# vco-8038.net
KiCad netlist of a schematic drawn in EAGLE
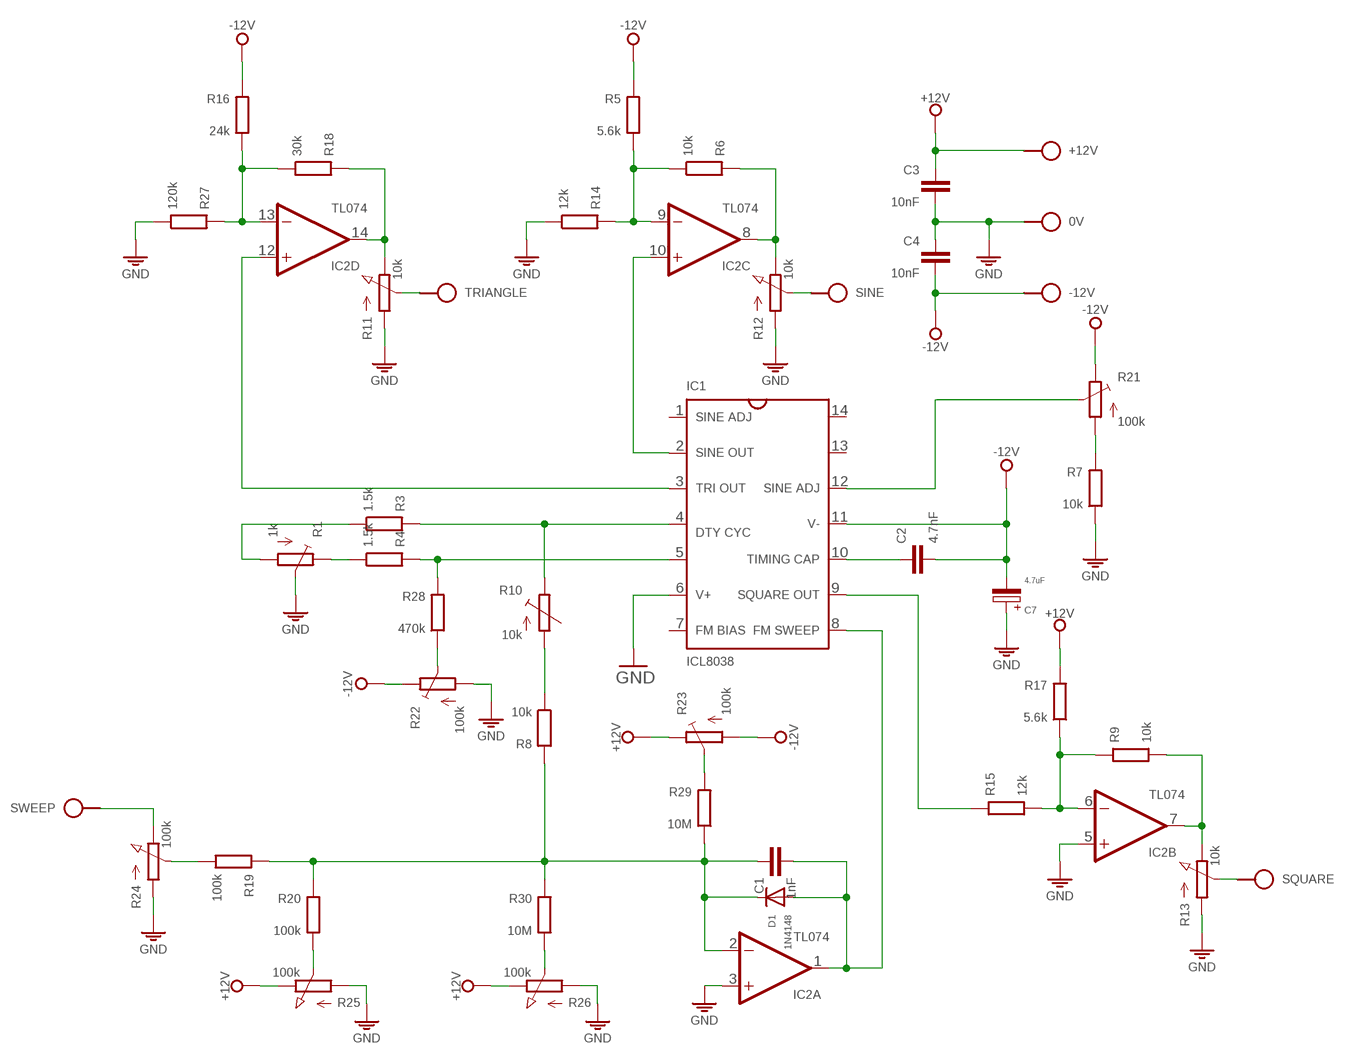
[diagram p0: schematic, sheet 1]

(export (version "E")
  (design (tool "Eeschema 10.0.6"))
  (components
    (comp (ref "+12V")
      (value "SPAD")
      (footprint "eagle-import:SPAD")
      (libsource (lib "eagle-import") (part "SPAD"))
    )
    (comp (ref "-12V")
      (value "SPAD")
      (footprint "eagle-import:SPAD")
      (libsource (lib "eagle-import") (part "SPAD"))
    )
    (comp (ref "0V")
      (value "SPAD")
      (footprint "eagle-import:SPAD")
      (libsource (lib "eagle-import") (part "SPAD"))
    )
    (comp (ref "C1")
      (value "1nF")
      (footprint "eagle-import:C050-020X036")
      (libsource (lib "eagle-import") (part "C050-020X036"))
    )
    (comp (ref "C2")
      (value "4.7nF")
      (footprint "eagle-import:C050-020X036")
      (libsource (lib "eagle-import") (part "C050-020X036"))
    )
    (comp (ref "C3")
      (value "10nF")
      (footprint "eagle-import:C050-020X036")
      (libsource (lib "eagle-import") (part "C050-020X036"))
    )
    (comp (ref "C4")
      (value "10nF")
      (footprint "eagle-import:C050-020X036")
      (libsource (lib "eagle-import") (part "C050-020X036"))
    )
    (comp (ref "C7")
      (value "4.7uF")
      (footprint "eagle-import:E5-5_V")
      (libsource (lib "eagle-import") (part "CPOLE5-5/V"))
    )
    (comp (ref "D1")
      (value "1N4148")
      (footprint "eagle-import:DO34-7")
      (libsource (lib "eagle-import") (part "1N414834-7"))
    )
    (comp (ref "IC1")
      (value "ICL8038")
      (footprint "eagle-import:DIL14")
      (libsource (lib "eagle-import") (part "ICL8038"))
    )
    (comp (ref "IC2")
      (value "TL074")
      (footprint "eagle-import:DIL14")
      (libsource (lib "eagle-import") (part "TL074P"))
    )
    (comp (ref "R1")
      (value "1k")
      (footprint "eagle-import:R-TRIM")
      (libsource (lib "eagle-import") (part "TRIMR-TRIM"))
    )
    (comp (ref "R3")
      (value "1.5k")
      (footprint "eagle-import:0204_7")
      (libsource (lib "eagle-import") (part "R0204/7"))
    )
    (comp (ref "R4")
      (value "1.5k")
      (footprint "eagle-import:0204_7")
      (libsource (lib "eagle-import") (part "R0204/7"))
    )
    (comp (ref "R5")
      (value "5.6k")
      (footprint "eagle-import:0204_7")
      (libsource (lib "eagle-import") (part "R0204/7"))
    )
    (comp (ref "R6")
      (value "10k")
      (footprint "eagle-import:0204_7")
      (libsource (lib "eagle-import") (part "R0204/7"))
    )
    (comp (ref "R7")
      (value "10k")
      (footprint "eagle-import:0204_7")
      (libsource (lib "eagle-import") (part "R0204/7"))
    )
    (comp (ref "R8")
      (value "10k")
      (footprint "eagle-import:0204_7")
      (libsource (lib "eagle-import") (part "R0204/7"))
    )
    (comp (ref "R9")
      (value "10k")
      (footprint "eagle-import:0204_7")
      (libsource (lib "eagle-import") (part "R0204/7"))
    )
    (comp (ref "R10")
      (value "10k")
      (footprint "eagle-import:R-TRIM")
      (libsource (lib "eagle-import") (part "TRIM-2R-TRIM-2"))
    )
    (comp (ref "R11")
      (value "10k")
      (footprint "eagle-import:POT")
      (libsource (lib "eagle-import") (part "POT"))
    )
    (comp (ref "R12")
      (value "10k")
      (footprint "eagle-import:POT")
      (libsource (lib "eagle-import") (part "POT"))
    )
    (comp (ref "R13")
      (value "10k")
      (footprint "eagle-import:POT")
      (libsource (lib "eagle-import") (part "POT"))
    )
    (comp (ref "R14")
      (value "12k")
      (footprint "eagle-import:0204_7")
      (libsource (lib "eagle-import") (part "R0204/7"))
    )
    (comp (ref "R15")
      (value "12k")
      (footprint "eagle-import:0204_7")
      (libsource (lib "eagle-import") (part "R0204/7"))
    )
    (comp (ref "R16")
      (value "24k")
      (footprint "eagle-import:0204_7")
      (libsource (lib "eagle-import") (part "R0204/7"))
    )
    (comp (ref "R17")
      (value "5.6k")
      (footprint "eagle-import:0204_7")
      (libsource (lib "eagle-import") (part "R0204/7"))
    )
    (comp (ref "R18")
      (value "30k")
      (footprint "eagle-import:0204_7")
      (libsource (lib "eagle-import") (part "R0204/7"))
    )
    (comp (ref "R19")
      (value "100k")
      (footprint "eagle-import:0204_7")
      (libsource (lib "eagle-import") (part "R0204/7"))
    )
    (comp (ref "R20")
      (value "100k")
      (footprint "eagle-import:0204_7")
      (libsource (lib "eagle-import") (part "R0204/7"))
    )
    (comp (ref "R21")
      (value "100k")
      (footprint "eagle-import:R-TRIM")
      (libsource (lib "eagle-import") (part "TRIMR-TRIM"))
    )
    (comp (ref "R22")
      (value "100k")
      (footprint "eagle-import:R-TRIM")
      (libsource (lib "eagle-import") (part "TRIMR-TRIM"))
    )
    (comp (ref "R23")
      (value "100k")
      (footprint "eagle-import:R-TRIM")
      (libsource (lib "eagle-import") (part "TRIMR-TRIM"))
    )
    (comp (ref "R24")
      (value "100k")
      (footprint "eagle-import:POT")
      (libsource (lib "eagle-import") (part "POT"))
    )
    (comp (ref "R25")
      (value "100k")
      (footprint "eagle-import:POT")
      (libsource (lib "eagle-import") (part "POT"))
    )
    (comp (ref "R26")
      (value "100k")
      (footprint "eagle-import:POT")
      (libsource (lib "eagle-import") (part "POT"))
    )
    (comp (ref "R27")
      (value "120k")
      (footprint "eagle-import:0204_7")
      (libsource (lib "eagle-import") (part "R0204/7"))
    )
    (comp (ref "R28")
      (value "470k")
      (footprint "eagle-import:0204_7")
      (libsource (lib "eagle-import") (part "R0204/7"))
    )
    (comp (ref "R29")
      (value "10M")
      (footprint "eagle-import:0204_7")
      (libsource (lib "eagle-import") (part "R0204/7"))
    )
    (comp (ref "R30")
      (value "10M")
      (footprint "eagle-import:0204_7")
      (libsource (lib "eagle-import") (part "R0204/7"))
    )
    (comp (ref "SINE")
      (value "SPAD")
      (footprint "eagle-import:SPAD")
      (libsource (lib "eagle-import") (part "SPAD"))
    )
    (comp (ref "SQUARE")
      (value "SPAD")
      (footprint "eagle-import:SPAD")
      (libsource (lib "eagle-import") (part "SPAD"))
    )
    (comp (ref "SWEEP")
      (value "SPAD")
      (footprint "eagle-import:SPAD")
      (libsource (lib "eagle-import") (part "SPAD"))
    )
    (comp (ref "TRIANGLE")
      (value "SPAD")
      (footprint "eagle-import:SPAD")
      (libsource (lib "eagle-import") (part "SPAD"))
    )
  )
  (nets
    (net (code "1") (name "+12V") (class "Default")
      (node (ref "+12V") (pin "1") (pinfunction "P$1_1") (pintype "bidirectional"))
      (node (ref "C3") (pin "1") (pinfunction "1_1") (pintype "passive"))
      (node (ref "R17") (pin "2") (pinfunction "2_2") (pintype "passive"))
      (node (ref "R23") (pin "3") (pinfunction "E_3") (pintype "passive"))
      (node (ref "R25") (pin "3") (pinfunction "E_3") (pintype "passive"))
      (node (ref "R26") (pin "3") (pinfunction "E_3") (pintype "passive"))
    )
    (net (code "2") (name "-12V") (class "Default")
      (node (ref "-12V") (pin "1") (pinfunction "P$1_1") (pintype "bidirectional"))
      (node (ref "C2") (pin "2") (pinfunction "2_2") (pintype "passive"))
      (node (ref "C4") (pin "2") (pinfunction "2_2") (pintype "passive"))
      (node (ref "C7") (pin "-") (pinfunction "-_-") (pintype "passive"))
      (node (ref "IC1") (pin "11") (pinfunction "V-_11") (pintype "bidirectional"))
      (node (ref "R16") (pin "2") (pinfunction "2_2") (pintype "passive"))
      (node (ref "R21") (pin "3") (pinfunction "E_3") (pintype "passive"))
      (node (ref "R22") (pin "3") (pinfunction "E_3") (pintype "passive"))
      (node (ref "R23") (pin "1") (pinfunction "A_1") (pintype "passive"))
      (node (ref "R5") (pin "2") (pinfunction "2_2") (pintype "passive"))
    )
    (net (code "3") (name "GND") (class "Default")
      (node (ref "0V") (pin "1") (pinfunction "P$1_1") (pintype "bidirectional"))
      (node (ref "C3") (pin "2") (pinfunction "2_2") (pintype "passive"))
      (node (ref "C4") (pin "1") (pinfunction "1_1") (pintype "passive"))
      (node (ref "C7") (pin "+") (pinfunction "+_+") (pintype "passive"))
      (node (ref "IC1") (pin "6") (pinfunction "V+_6") (pintype "bidirectional"))
      (node (ref "IC2") (pin "3") (pinfunction "+IN_3") (pintype "input"))
      (node (ref "IC2") (pin "5") (pinfunction "+IN_5") (pintype "input"))
      (node (ref "R1") (pin "2") (pinfunction "S_2") (pintype "passive"))
      (node (ref "R11") (pin "1") (pinfunction "A_1") (pintype "passive"))
      (node (ref "R12") (pin "1") (pinfunction "A_1") (pintype "passive"))
      (node (ref "R13") (pin "1") (pinfunction "A_1") (pintype "passive"))
      (node (ref "R14") (pin "1") (pinfunction "1_1") (pintype "passive"))
      (node (ref "R22") (pin "1") (pinfunction "A_1") (pintype "passive"))
      (node (ref "R24") (pin "1") (pinfunction "A_1") (pintype "passive"))
      (node (ref "R25") (pin "1") (pinfunction "A_1") (pintype "passive"))
      (node (ref "R26") (pin "1") (pinfunction "A_1") (pintype "passive"))
      (node (ref "R27") (pin "1") (pinfunction "1_1") (pintype "passive"))
      (node (ref "R7") (pin "1") (pinfunction "1_1") (pintype "passive"))
    )
    (net (code "4") (name "Net-(IC1-DUTY_1)") (class "Default")
      (node (ref "IC1") (pin "4") (pinfunction "DUTY_1_4") (pintype "bidirectional"))
      (node (ref "R10") (pin "1") (pinfunction "1_1") (pintype "passive"))
      (node (ref "R10") (pin "2") (pinfunction "1_2") (pintype "passive"))
      (node (ref "R3") (pin "2") (pinfunction "2_2") (pintype "passive"))
    )
    (net (code "5") (name "Net-(IC1-DUTY_2)") (class "Default")
      (node (ref "IC1") (pin "5") (pinfunction "DUTY_2_5") (pintype "bidirectional"))
      (node (ref "R28") (pin "2") (pinfunction "2_2") (pintype "passive"))
      (node (ref "R4") (pin "2") (pinfunction "2_2") (pintype "passive"))
    )
    (net (code "6") (name "Net-(IC1-FM_SWEEP)") (class "Default")
      (node (ref "C1") (pin "2") (pinfunction "2_2") (pintype "passive"))
      (node (ref "D1") (pin "A") (pinfunction "A_A") (pintype "passive"))
      (node (ref "IC1") (pin "8") (pinfunction "FM_SWEEP_8") (pintype "bidirectional"))
      (node (ref "IC2") (pin "1") (pinfunction "OUT_1") (pintype "output"))
    )
    (net (code "7") (name "Net-(IC1-SINE_ADJ_2)") (class "Default")
      (node (ref "IC1") (pin "12") (pinfunction "SINE_ADJ_2_12") (pintype "bidirectional"))
      (node (ref "R21") (pin "2") (pinfunction "S_2") (pintype "passive"))
    )
    (net (code "8") (name "Net-(IC1-SINE_OUT)") (class "Default")
      (node (ref "IC1") (pin "2") (pinfunction "SINE_OUT_2") (pintype "bidirectional"))
      (node (ref "IC2") (pin "10") (pinfunction "+IN_10") (pintype "input"))
    )
    (net (code "9") (name "Net-(IC1-SQR_OUT)") (class "Default")
      (node (ref "IC1") (pin "9") (pinfunction "SQR_OUT_9") (pintype "bidirectional"))
      (node (ref "R15") (pin "2") (pinfunction "2_2") (pintype "passive"))
    )
    (net (code "10") (name "Net-(IC1-TIMING_CAP)") (class "Default")
      (node (ref "C2") (pin "1") (pinfunction "1_1") (pintype "passive"))
      (node (ref "IC1") (pin "10") (pinfunction "TIMING_CAP_10") (pintype "bidirectional"))
    )
    (net (code "11") (name "Net-(IC1-TRI_OUT)") (class "Default")
      (node (ref "IC1") (pin "3") (pinfunction "TRI_OUT_3") (pintype "bidirectional"))
      (node (ref "IC2") (pin "12") (pinfunction "+IN_12") (pintype "input"))
    )
    (net (code "12") (name "Net-(IC2A--IN)") (class "Default")
      (node (ref "C1") (pin "1") (pinfunction "1_1") (pintype "passive"))
      (node (ref "D1") (pin "C") (pinfunction "C_C") (pintype "passive"))
      (node (ref "IC2") (pin "2") (pinfunction "-IN_2") (pintype "input"))
      (node (ref "R19") (pin "2") (pinfunction "2_2") (pintype "passive"))
      (node (ref "R20") (pin "2") (pinfunction "2_2") (pintype "passive"))
      (node (ref "R29") (pin "1") (pinfunction "1_1") (pintype "passive"))
      (node (ref "R30") (pin "2") (pinfunction "2_2") (pintype "passive"))
      (node (ref "R8") (pin "2") (pinfunction "2_2") (pintype "passive"))
    )
    (net (code "13") (name "Net-(IC2B--IN)") (class "Default")
      (node (ref "IC2") (pin "6") (pinfunction "-IN_6") (pintype "input"))
      (node (ref "R15") (pin "1") (pinfunction "1_1") (pintype "passive"))
      (node (ref "R17") (pin "1") (pinfunction "1_1") (pintype "passive"))
      (node (ref "R9") (pin "2") (pinfunction "2_2") (pintype "passive"))
    )
    (net (code "14") (name "Net-(IC2B-OUT)") (class "Default")
      (node (ref "IC2") (pin "7") (pinfunction "OUT_7") (pintype "output"))
      (node (ref "R13") (pin "3") (pinfunction "E_3") (pintype "passive"))
      (node (ref "R9") (pin "1") (pinfunction "1_1") (pintype "passive"))
    )
    (net (code "15") (name "Net-(IC2C--IN)") (class "Default")
      (node (ref "IC2") (pin "9") (pinfunction "-IN_9") (pintype "input"))
      (node (ref "R14") (pin "2") (pinfunction "2_2") (pintype "passive"))
      (node (ref "R5") (pin "1") (pinfunction "1_1") (pintype "passive"))
      (node (ref "R6") (pin "1") (pinfunction "1_1") (pintype "passive"))
    )
    (net (code "16") (name "Net-(IC2C-OUT)") (class "Default")
      (node (ref "IC2") (pin "8") (pinfunction "OUT_8") (pintype "output"))
      (node (ref "R12") (pin "3") (pinfunction "E_3") (pintype "passive"))
      (node (ref "R6") (pin "2") (pinfunction "2_2") (pintype "passive"))
    )
    (net (code "17") (name "Net-(IC2D--IN)") (class "Default")
      (node (ref "IC2") (pin "13") (pinfunction "-IN_13") (pintype "input"))
      (node (ref "R16") (pin "1") (pinfunction "1_1") (pintype "passive"))
      (node (ref "R18") (pin "1") (pinfunction "1_1") (pintype "passive"))
      (node (ref "R27") (pin "2") (pinfunction "2_2") (pintype "passive"))
    )
    (net (code "18") (name "Net-(IC2D-OUT)") (class "Default")
      (node (ref "IC2") (pin "14") (pinfunction "OUT_14") (pintype "output"))
      (node (ref "R11") (pin "3") (pinfunction "E_3") (pintype "passive"))
      (node (ref "R18") (pin "2") (pinfunction "2_2") (pintype "passive"))
    )
    (net (code "19") (name "Net-(R1-A)") (class "Default")
      (node (ref "R1") (pin "1") (pinfunction "A_1") (pintype "passive"))
      (node (ref "R3") (pin "1") (pinfunction "1_1") (pintype "passive"))
    )
    (net (code "20") (name "Net-(R1-E)") (class "Default")
      (node (ref "R1") (pin "3") (pinfunction "E_3") (pintype "passive"))
      (node (ref "R4") (pin "1") (pinfunction "1_1") (pintype "passive"))
    )
    (net (code "21") (name "Net-(R10-2)") (class "Default")
      (node (ref "R10") (pin "3") (pinfunction "2_3") (pintype "passive"))
      (node (ref "R8") (pin "1") (pinfunction "1_1") (pintype "passive"))
    )
    (net (code "22") (name "Net-(R11-S)") (class "Default")
      (node (ref "R11") (pin "2") (pinfunction "S_2") (pintype "passive"))
      (node (ref "TRIANGLE") (pin "1") (pinfunction "P$1_1") (pintype "bidirectional"))
    )
    (net (code "23") (name "Net-(R12-S)") (class "Default")
      (node (ref "R12") (pin "2") (pinfunction "S_2") (pintype "passive"))
      (node (ref "SINE") (pin "1") (pinfunction "P$1_1") (pintype "bidirectional"))
    )
    (net (code "24") (name "Net-(R13-S)") (class "Default")
      (node (ref "R13") (pin "2") (pinfunction "S_2") (pintype "passive"))
      (node (ref "SQUARE") (pin "1") (pinfunction "P$1_1") (pintype "bidirectional"))
    )
    (net (code "25") (name "Net-(R21-A)") (class "Default")
      (node (ref "R21") (pin "1") (pinfunction "A_1") (pintype "passive"))
      (node (ref "R7") (pin "2") (pinfunction "2_2") (pintype "passive"))
    )
    (net (code "26") (name "Net-(R22-S)") (class "Default")
      (node (ref "R22") (pin "2") (pinfunction "S_2") (pintype "passive"))
      (node (ref "R28") (pin "1") (pinfunction "1_1") (pintype "passive"))
    )
    (net (code "27") (name "Net-(R23-S)") (class "Default")
      (node (ref "R23") (pin "2") (pinfunction "S_2") (pintype "passive"))
      (node (ref "R29") (pin "2") (pinfunction "2_2") (pintype "passive"))
    )
    (net (code "28") (name "Net-(R24-E)") (class "Default")
      (node (ref "R24") (pin "3") (pinfunction "E_3") (pintype "passive"))
      (node (ref "SWEEP") (pin "1") (pinfunction "P$1_1") (pintype "bidirectional"))
    )
    (net (code "29") (name "Net-(R24-S)") (class "Default")
      (node (ref "R19") (pin "1") (pinfunction "1_1") (pintype "passive"))
      (node (ref "R24") (pin "2") (pinfunction "S_2") (pintype "passive"))
    )
    (net (code "30") (name "Net-(R25-S)") (class "Default")
      (node (ref "R20") (pin "1") (pinfunction "1_1") (pintype "passive"))
      (node (ref "R25") (pin "2") (pinfunction "S_2") (pintype "passive"))
    )
    (net (code "31") (name "Net-(R26-S)") (class "Default")
      (node (ref "R26") (pin "2") (pinfunction "S_2") (pintype "passive"))
      (node (ref "R30") (pin "1") (pinfunction "1_1") (pintype "passive"))
    )
    (net (code "32") (name "unconnected-(IC1-FM_BIAS-Pad7)") (class "Default")
      (node (ref "IC1") (pin "7") (pinfunction "FM_BIAS_7") (pintype "bidirectional"))
    )
    (net (code "33") (name "unconnected-(IC1-NC_1-Pad13)") (class "Default")
      (node (ref "IC1") (pin "13") (pinfunction "NC_1_13") (pintype "bidirectional"))
    )
    (net (code "34") (name "unconnected-(IC1-NC_2-Pad14)") (class "Default")
      (node (ref "IC1") (pin "14") (pinfunction "NC_2_14") (pintype "bidirectional"))
    )
    (net (code "35") (name "unconnected-(IC1-SINE_ADJ-Pad1)") (class "Default")
      (node (ref "IC1") (pin "1") (pinfunction "SINE_ADJ_1") (pintype "bidirectional"))
    )
  )
)
